# sign_controller.net
KiCad netlist of a schematic drawn in Altium Designer
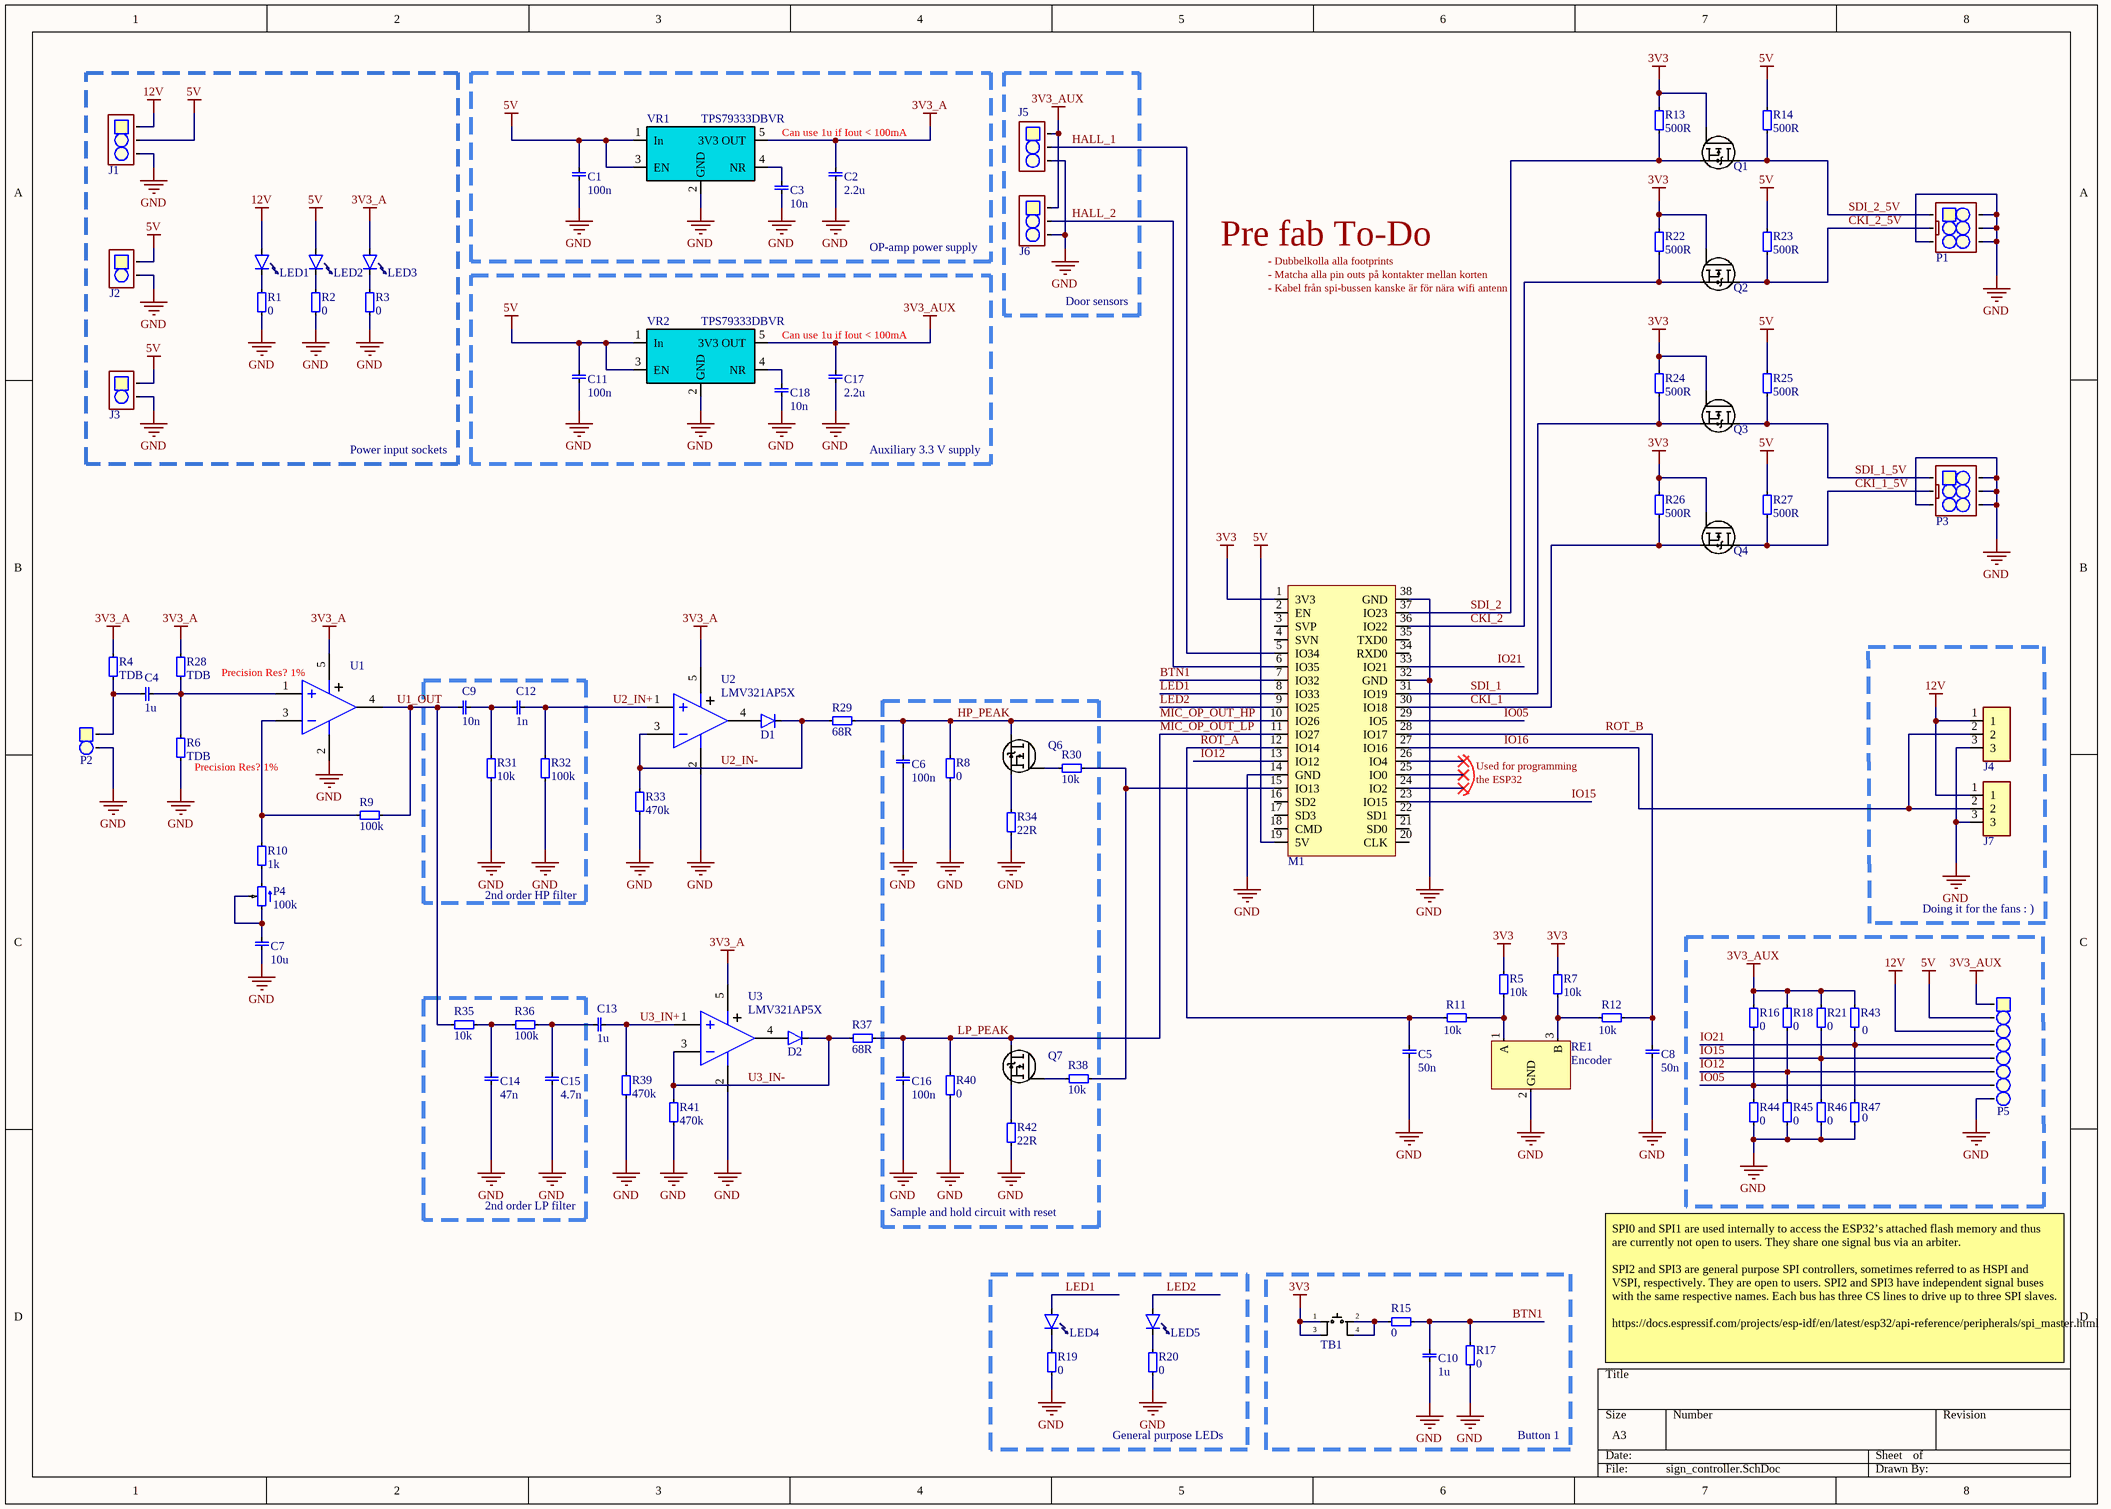
[diagram p0: sign_controller.SchDoc]

(export (version "E")
  (design (tool "Eeschema 10.0.6"))
  (components
    (comp (ref "C1")
      (value "100n")
      (footprint "0603 cap")
      (fields (field (name "Comment") "0603, capacitor"))
      (libsource (lib "sign_lib") (part "0603, capacitor"))
    )
    (comp (ref "C2")
      (value "2.2u")
      (footprint "1206, capasitor")
      (fields (field (name "Comment") "1206, capacitor"))
      (libsource (lib "sign_lib") (part "1206, capacitor"))
    )
    (comp (ref "C3")
      (value "10n")
      (footprint "0603 cap")
      (fields (field (name "Comment") "0603, capacitor"))
      (libsource (lib "sign_lib") (part "0603, capacitor"))
    )
    (comp (ref "C4")
      (value "1u")
      (footprint "1206, capasitor")
      (fields (field (name "Comment") "1206, capacitor"))
      (libsource (lib "sign_lib") (part "1206, capacitor"))
    )
    (comp (ref "C5")
      (value "50n")
      (footprint "0603 cap")
      (fields (field (name "Comment") "0603, capacitor"))
      (libsource (lib "sign_lib") (part "0603, capacitor"))
    )
    (comp (ref "C6")
      (value "100n")
      (footprint "0603 cap")
      (fields (field (name "Comment") "0603, capacitor"))
      (libsource (lib "sign_lib") (part "0603, capacitor"))
    )
    (comp (ref "C7")
      (value "10u")
      (footprint "1206, capasitor")
      (fields (field (name "Comment") "1206, capacitor"))
      (libsource (lib "sign_lib") (part "1206, capacitor"))
    )
    (comp (ref "C8")
      (value "50n")
      (footprint "0603 cap")
      (fields (field (name "Comment") "0603, capacitor"))
      (libsource (lib "sign_lib") (part "0603, capacitor"))
    )
    (comp (ref "C9")
      (value "10n")
      (footprint "0603 cap")
      (fields (field (name "Comment") "0603, capacitor"))
      (libsource (lib "sign_lib") (part "0603, capacitor"))
    )
    (comp (ref "C10")
      (value "1u")
      (footprint "0603 cap")
      (fields (field (name "Comment") "0603, capacitor"))
      (libsource (lib "jclib") (part "0603, capacitor"))
    )
    (comp (ref "C11")
      (value "100n")
      (footprint "0603 cap")
      (fields (field (name "Comment") "0603, capacitor"))
      (libsource (lib "sign_lib") (part "0603, capacitor"))
    )
    (comp (ref "C12")
      (value "1n")
      (footprint "0603 cap")
      (fields (field (name "Comment") "0603, capacitor"))
      (libsource (lib "sign_lib") (part "0603, capacitor"))
    )
    (comp (ref "C13")
      (value "1u")
      (footprint "0603 cap")
      (fields (field (name "Comment") "0603, capacitor"))
      (libsource (lib "sign_lib") (part "0603, capacitor"))
    )
    (comp (ref "C14")
      (value "47n")
      (footprint "0603 cap")
      (fields (field (name "Comment") "0603, capacitor"))
      (libsource (lib "sign_lib") (part "0603, capacitor"))
    )
    (comp (ref "C15")
      (value "4.7n")
      (footprint "0603 cap")
      (fields (field (name "Comment") "0603, capacitor"))
      (libsource (lib "sign_lib") (part "0603, capacitor"))
    )
    (comp (ref "C16")
      (value "100n")
      (footprint "0603 cap")
      (fields (field (name "Comment") "0603, capacitor"))
      (libsource (lib "sign_lib") (part "0603, capacitor"))
    )
    (comp (ref "C17")
      (value "2.2u")
      (footprint "1206, capasitor")
      (fields (field (name "Comment") "1206, capacitor"))
      (libsource (lib "sign_lib") (part "1206, capacitor"))
    )
    (comp (ref "C18")
      (value "10n")
      (footprint "0603 cap")
      (fields (field (name "Comment") "0603, capacitor"))
      (libsource (lib "sign_lib") (part "0603, capacitor"))
    )
    (comp (ref "D1")
      (value "BAT18")
      (footprint "SOT23")
      (description "Electrokit art: 40311018, 100mA, Vf 1.2V, 35V")
      (libsource (lib "sign_lib") (part "Diode SMD"))
    )
    (comp (ref "D2")
      (value "BAT18")
      (footprint "SOT23")
      (description "Electrokit art: 40311018, 100mA, Vf 1.2V, 35V")
      (libsource (lib "sign_lib") (part "Diode SMD"))
    )
    (comp (ref "J1")
      (value "3 Pole MSTBA Connector")
      (footprint "3POLE_MSTBA_ANGLE")
      (libsource (lib "sign_lib") (part "3 Pole MSTBA Connector"))
    )
    (comp (ref "J2")
      (value "2 Pole MSTBA Connector")
      (footprint "2POLE_MSTBA_ANGLE")
      (libsource (lib "sign_lib") (part "2 Pole MSTBA Connector"))
    )
    (comp (ref "J3")
      (value "2 Pole MSTBA Connector")
      (footprint "2POLE_MSTBA_ANGLE")
      (libsource (lib "sign_lib") (part "2 Pole MSTBA Connector"))
    )
    (comp (ref "J4")
      (value "PicoBlade, 3 pos")
      (footprint "MOLEX_0530470310")
      (libsource (lib "exensor_lib") (part "PicoBlade, 3 pos"))
    )
    (comp (ref "J5")
      (value "3 Pole MSTBA Connector")
      (footprint "3POLE_MSTBA_ANGLE")
      (libsource (lib "sign_lib") (part "3 Pole MSTBA Connector"))
    )
    (comp (ref "J6")
      (value "3 Pole MSTBA Connector")
      (footprint "3POLE_MSTBA_ANGLE")
      (libsource (lib "sign_lib") (part "3 Pole MSTBA Connector"))
    )
    (comp (ref "J7")
      (value "PicoBlade, 3 pos")
      (footprint "MOLEX_0530470310")
      (libsource (lib "exensor_lib") (part "PicoBlade, 3 pos"))
    )
    (comp (ref "LED1")
      (value "0805, LED")
      (footprint "0805_led")
      (libsource (lib "sign_lib") (part "0805, LED"))
    )
    (comp (ref "LED2")
      (value "0805, LED")
      (footprint "0805_led")
      (libsource (lib "sign_lib") (part "0805, LED"))
    )
    (comp (ref "LED3")
      (value "0805, LED")
      (footprint "0805_led")
      (libsource (lib "sign_lib") (part "0805, LED"))
    )
    (comp (ref "LED4")
      (value "0805, LED")
      (footprint "0805_led")
      (libsource (lib "sign_lib") (part "0805, LED"))
    )
    (comp (ref "LED5")
      (value "0805, LED")
      (footprint "0805_led")
      (libsource (lib "sign_lib") (part "0805, LED"))
    )
    (comp (ref "M1")
      (value "ESP32-DEVKITC-32D-F")
      (footprint "ESP32_DEVKITC")
      (libsource (lib "sign_lib") (part "ESP32-DEVKITC-32D-F"))
    )
    (comp (ref "P1")
      (value "2x3 Pin Header")
      (footprint "2x3 PH")
      (description "2x3 Ribbon connector")
      (libsource (lib "sign_lib") (part "2x3 Ribbon connector"))
    )
    (comp (ref "P2")
      (value "1x2 Pin Header")
      (footprint "padtwo_L")
      (description "2.54 mm, TH")
      (libsource (lib "sign_lib") (part "1x2 Pin Header"))
    )
    (comp (ref "P3")
      (value "2x3 Pin Header")
      (footprint "2x3 PH")
      (description "2x3 Ribbon connector")
      (libsource (lib "sign_lib") (part "2x3 Ribbon connector"))
    )
    (comp (ref "P4")
      (value "100k")
      (footprint "POT_TH1")
      (fields (field (name "Comment") "Pot"))
      (libsource (lib "sign_lib") (part "Pot"))
    )
    (comp (ref "P5")
      (value "1x8 Pin Header")
      (footprint "1x8 Pin HEader")
      (description "2.54 mm")
      (libsource (lib "sign_lib") (part "1x8 Pin Header"))
    )
    (comp (ref "Q1")
      (value "BSS138")
      (footprint "SOT323")
      (description "N-Channel Logic Level Enhancement Mode Field Effect Transistor")
      (libsource (lib "sign_lib") (part "BSS138"))
    )
    (comp (ref "Q2")
      (value "BSS138")
      (footprint "SOT323")
      (description "N-Channel Logic Level Enhancement Mode Field Effect Transistor")
      (libsource (lib "sign_lib") (part "BSS138"))
    )
    (comp (ref "Q3")
      (value "BSS138")
      (footprint "SOT323")
      (description "N-Channel Logic Level Enhancement Mode Field Effect Transistor")
      (libsource (lib "sign_lib") (part "BSS138"))
    )
    (comp (ref "Q4")
      (value "BSS138")
      (footprint "SOT323")
      (description "N-Channel Logic Level Enhancement Mode Field Effect Transistor")
      (libsource (lib "sign_lib") (part "BSS138"))
    )
    (comp (ref "Q6")
      (value "BSS138")
      (footprint "SOT323")
      (description "N-Channel Logic Level Enhancement Mode Field Effect Transistor")
      (libsource (lib "sign_lib") (part "BSS138"))
    )
    (comp (ref "Q7")
      (value "BSS138")
      (footprint "SOT323")
      (description "N-Channel Logic Level Enhancement Mode Field Effect Transistor")
      (libsource (lib "sign_lib") (part "BSS138"))
    )
    (comp (ref "R1")
      (value "0")
      (footprint "0603")
      (fields (field (name "Comment") "0603, resistor"))
      (libsource (lib "sign_lib") (part "0603, resistor"))
    )
    (comp (ref "R2")
      (value "0")
      (footprint "0603")
      (fields (field (name "Comment") "0603, resistor"))
      (libsource (lib "sign_lib") (part "0603, resistor"))
    )
    (comp (ref "R3")
      (value "0")
      (footprint "0603")
      (fields (field (name "Comment") "0603, resistor"))
      (libsource (lib "sign_lib") (part "0603, resistor"))
    )
    (comp (ref "R4")
      (value "TDB")
      (footprint "0603")
      (fields (field (name "Comment") "0603, resistor"))
      (libsource (lib "sign_lib") (part "0603, resistor"))
    )
    (comp (ref "R5")
      (value "10k")
      (footprint "0603")
      (fields (field (name "Comment") "0603, resistor"))
      (libsource (lib "sign_lib") (part "0603, resistor"))
    )
    (comp (ref "R6")
      (value "TDB")
      (footprint "0603")
      (fields (field (name "Comment") "0603, resistor"))
      (libsource (lib "sign_lib") (part "0603, resistor"))
    )
    (comp (ref "R7")
      (value "10k")
      (footprint "0603")
      (fields (field (name "Comment") "0603, resistor"))
      (libsource (lib "sign_lib") (part "0603, resistor"))
    )
    (comp (ref "R8")
      (value "0")
      (footprint "0603")
      (fields (field (name "Comment") "0603, resistor"))
      (libsource (lib "sign_lib") (part "0603, resistor"))
    )
    (comp (ref "R9")
      (value "100k")
      (footprint "0603")
      (fields (field (name "Comment") "0603, resistor"))
      (libsource (lib "sign_lib") (part "0603, resistor"))
    )
    (comp (ref "R10")
      (value "1k")
      (footprint "0603")
      (fields (field (name "Comment") "0603, resistor"))
      (libsource (lib "sign_lib") (part "0603, resistor"))
    )
    (comp (ref "R11")
      (value "10k")
      (footprint "0603")
      (fields (field (name "Comment") "0603, resistor"))
      (libsource (lib "sign_lib") (part "0603, resistor"))
    )
    (comp (ref "R12")
      (value "10k")
      (footprint "0603")
      (fields (field (name "Comment") "0603, resistor"))
      (libsource (lib "sign_lib") (part "0603, resistor"))
    )
    (comp (ref "R13")
      (value "500R")
      (footprint "0603")
      (fields (field (name "Comment") "0603, resistor"))
      (libsource (lib "sign_lib") (part "0603, resistor"))
    )
    (comp (ref "R14")
      (value "500R")
      (footprint "0603")
      (fields (field (name "Comment") "0603, resistor"))
      (libsource (lib "sign_lib") (part "0603, resistor"))
    )
    (comp (ref "R15")
      (value "0")
      (footprint "0603")
      (fields (field (name "Comment") "0603, resistor"))
      (libsource (lib "sign_lib") (part "0603, resistor"))
    )
    (comp (ref "R16")
      (value "0")
      (footprint "0603")
      (fields (field (name "Comment") "0603, resistor"))
      (libsource (lib "sign_lib") (part "0603, resistor"))
    )
    (comp (ref "R17")
      (value "0")
      (footprint "0603")
      (fields (field (name "Comment") "0603, resistor"))
      (libsource (lib "sign_lib") (part "0603, resistor"))
    )
    (comp (ref "R18")
      (value "0")
      (footprint "0603")
      (fields (field (name "Comment") "0603, resistor"))
      (libsource (lib "sign_lib") (part "0603, resistor"))
    )
    (comp (ref "R19")
      (value "0")
      (footprint "0603")
      (fields (field (name "Comment") "0603, resistor"))
      (libsource (lib "sign_lib") (part "0603, resistor"))
    )
    (comp (ref "R20")
      (value "0")
      (footprint "0603")
      (fields (field (name "Comment") "0603, resistor"))
      (libsource (lib "sign_lib") (part "0603, resistor"))
    )
    (comp (ref "R21")
      (value "0")
      (footprint "0603")
      (fields (field (name "Comment") "0603, resistor"))
      (libsource (lib "sign_lib") (part "0603, resistor"))
    )
    (comp (ref "R22")
      (value "500R")
      (footprint "0603")
      (fields (field (name "Comment") "0603, resistor"))
      (libsource (lib "sign_lib") (part "0603, resistor"))
    )
    (comp (ref "R23")
      (value "500R")
      (footprint "0603")
      (fields (field (name "Comment") "0603, resistor"))
      (libsource (lib "sign_lib") (part "0603, resistor"))
    )
    (comp (ref "R24")
      (value "500R")
      (footprint "0603")
      (fields (field (name "Comment") "0603, resistor"))
      (libsource (lib "sign_lib") (part "0603, resistor"))
    )
    (comp (ref "R25")
      (value "500R")
      (footprint "0603")
      (fields (field (name "Comment") "0603, resistor"))
      (libsource (lib "sign_lib") (part "0603, resistor"))
    )
    (comp (ref "R26")
      (value "500R")
      (footprint "0603")
      (fields (field (name "Comment") "0603, resistor"))
      (libsource (lib "sign_lib") (part "0603, resistor"))
    )
    (comp (ref "R27")
      (value "500R")
      (footprint "0603")
      (fields (field (name "Comment") "0603, resistor"))
      (libsource (lib "sign_lib") (part "0603, resistor"))
    )
    (comp (ref "R28")
      (value "TDB")
      (footprint "0603")
      (fields (field (name "Comment") "0603, resistor"))
      (libsource (lib "sign_lib") (part "0603, resistor"))
    )
    (comp (ref "R29")
      (value "68R")
      (footprint "0603")
      (fields (field (name "Comment") "0603, resistor"))
      (libsource (lib "sign_lib") (part "0603, resistor"))
    )
    (comp (ref "R30")
      (value "10k")
      (footprint "0603")
      (fields (field (name "Comment") "0603, resistor"))
      (libsource (lib "sign_lib") (part "0603, resistor"))
    )
    (comp (ref "R31")
      (value "10k")
      (footprint "0603")
      (fields (field (name "Comment") "0603, resistor"))
      (libsource (lib "sign_lib") (part "0603, resistor"))
    )
    (comp (ref "R32")
      (value "100k")
      (footprint "0603")
      (fields (field (name "Comment") "0603, resistor"))
      (libsource (lib "sign_lib") (part "0603, resistor"))
    )
    (comp (ref "R33")
      (value "470k")
      (footprint "0603")
      (fields (field (name "Comment") "0603, resistor"))
      (libsource (lib "sign_lib") (part "0603, resistor"))
    )
    (comp (ref "R34")
      (value "22R")
      (footprint "0603")
      (fields (field (name "Comment") "0603, resistor"))
      (libsource (lib "sign_lib") (part "0603, resistor"))
    )
    (comp (ref "R35")
      (value "10k")
      (footprint "0603")
      (fields (field (name "Comment") "0603, resistor"))
      (libsource (lib "sign_lib") (part "0603, resistor"))
    )
    (comp (ref "R36")
      (value "100k")
      (footprint "0603")
      (fields (field (name "Comment") "0603, resistor"))
      (libsource (lib "sign_lib") (part "0603, resistor"))
    )
    (comp (ref "R37")
      (value "68R")
      (footprint "0603")
      (fields (field (name "Comment") "0603, resistor"))
      (libsource (lib "sign_lib") (part "0603, resistor"))
    )
    (comp (ref "R38")
      (value "10k")
      (footprint "0603")
      (fields (field (name "Comment") "0603, resistor"))
      (libsource (lib "sign_lib") (part "0603, resistor"))
    )
    (comp (ref "R39")
      (value "470k")
      (footprint "0603")
      (fields (field (name "Comment") "0603, resistor"))
      (libsource (lib "sign_lib") (part "0603, resistor"))
    )
    (comp (ref "R40")
      (value "0")
      (footprint "0603")
      (fields (field (name "Comment") "0603, resistor"))
      (libsource (lib "sign_lib") (part "0603, resistor"))
    )
    (comp (ref "R41")
      (value "470k")
      (footprint "0603")
      (fields (field (name "Comment") "0603, resistor"))
      (libsource (lib "sign_lib") (part "0603, resistor"))
    )
    (comp (ref "R42")
      (value "22R")
      (footprint "0603")
      (fields (field (name "Comment") "0603, resistor"))
      (libsource (lib "sign_lib") (part "0603, resistor"))
    )
    (comp (ref "R43")
      (value "0")
      (footprint "0603")
      (fields (field (name "Comment") "0603, resistor"))
      (libsource (lib "sign_lib") (part "0603, resistor"))
    )
    (comp (ref "R44")
      (value "0")
      (footprint "0603")
      (fields (field (name "Comment") "0603, resistor"))
      (libsource (lib "sign_lib") (part "0603, resistor"))
    )
    (comp (ref "R45")
      (value "0")
      (footprint "0603")
      (fields (field (name "Comment") "0603, resistor"))
      (libsource (lib "sign_lib") (part "0603, resistor"))
    )
    (comp (ref "R46")
      (value "0")
      (footprint "0603")
      (fields (field (name "Comment") "0603, resistor"))
      (libsource (lib "sign_lib") (part "0603, resistor"))
    )
    (comp (ref "R47")
      (value "0")
      (footprint "0603")
      (fields (field (name "Comment") "0603, resistor"))
      (libsource (lib "sign_lib") (part "0603, resistor"))
    )
    (comp (ref "RE1")
      (value "Encoder")
      (footprint "RotaryEncoder")
      (libsource (lib "sign_lib") (part "RotaryEncoder"))
    )
    (comp (ref "TB1")
      (value "Tactile Button")
      (footprint "tacButton smd")
      (description "Tactile Switch Small Low")
      (libsource (lib "sign_lib") (part "TacButton SMD"))
    )
    (comp (ref "U1")
      (value "LMV321AP5X")
      (footprint "SOT23-5")
      (description "Operational Amplifier, Low Power, Rail to Rail Output, CMOS Op-Amp")
      (fields (field (name "MANUFACTURER") "ON Semiconductor / Fairchild"))
      (libsource (lib "sign_lib") (part "LMV321AP5X"))
    )
    (comp (ref "U2")
      (value "LMV321AP5X")
      (footprint "SOT23-5")
      (description "Operational Amplifier, Low Power, Rail to Rail Output, CMOS Op-Amp")
      (fields (field (name "MANUFACTURER") "ON Semiconductor / Fairchild"))
      (libsource (lib "sign_lib") (part "LMV321AP5X"))
    )
    (comp (ref "U3")
      (value "LMV321AP5X")
      (footprint "SOT23-5")
      (description "Operational Amplifier, Low Power, Rail to Rail Output, CMOS Op-Amp")
      (fields (field (name "MANUFACTURER") "ON Semiconductor / Fairchild"))
      (libsource (lib "sign_lib") (part "LMV321AP5X"))
    )
    (comp (ref "VR1")
      (value "TPS79333DBVR")
      (footprint "SOT23-5")
      (description "Low Dropout Regulators(LDO) Positive Fixed 180mV @ 200mA 5.5V 3.3V 200mA SOT-23-5 RoHS")
      (fields (field (name "MANUFACTURER") "Texas Instruments"))
      (libsource (lib "sign_lib") (part "TPS79333DBVR"))
    )
    (comp (ref "VR2")
      (value "TPS79333DBVR")
      (footprint "SOT23-5")
      (description "Low Dropout Regulators(LDO) Positive Fixed 180mV @ 200mA 5.5V 3.3V 200mA SOT-23-5 RoHS")
      (fields (field (name "MANUFACTURER") "Texas Instruments"))
      (libsource (lib "sign_lib") (part "TPS79333DBVR"))
    )
  )
  (nets
    (net (code "1") (name "/BTN1") (class "Default")
      (node (ref "C10") (pin "1") (pinfunction "1_1") (pintype "passive"))
      (node (ref "M1") (pin "7") (pinfunction "IO32_7") (pintype "passive"))
      (node (ref "R15") (pin "0") (pinfunction "0_0") (pintype "passive"))
      (node (ref "R17") (pin "0") (pinfunction "0_0") (pintype "passive"))
    )
    (net (code "2") (name "/CKI_1") (class "Default")
      (node (ref "M1") (pin "30") (pinfunction "IO18_30") (pintype "passive"))
      (node (ref "Q4") (pin "2") (pinfunction "S_2") (pintype "passive"))
      (node (ref "R26") (pin "0") (pinfunction "0_0") (pintype "passive"))
    )
    (net (code "3") (name "/CKI_1_5V") (class "Default")
      (node (ref "P3") (pin "2") (pinfunction "2_2") (pintype "passive"))
      (node (ref "Q4") (pin "3") (pinfunction "D_3") (pintype "passive"))
      (node (ref "R27") (pin "0") (pinfunction "0_0") (pintype "passive"))
    )
    (net (code "4") (name "/CKI_2") (class "Default")
      (node (ref "M1") (pin "36") (pinfunction "IO22_36") (pintype "passive"))
      (node (ref "Q2") (pin "2") (pinfunction "S_2") (pintype "passive"))
      (node (ref "R22") (pin "0") (pinfunction "0_0") (pintype "passive"))
    )
    (net (code "5") (name "/CKI_2_5V") (class "Default")
      (node (ref "P1") (pin "2") (pinfunction "2_2") (pintype "passive"))
      (node (ref "Q2") (pin "3") (pinfunction "D_3") (pintype "passive"))
      (node (ref "R23") (pin "0") (pinfunction "0_0") (pintype "passive"))
    )
    (net (code "6") (name "/HALL_1") (class "Default")
      (node (ref "J5") (pin "2") (pinfunction "2_2") (pintype "passive"))
      (node (ref "M1") (pin "5") (pinfunction "IO34_5") (pintype "passive"))
    )
    (net (code "7") (name "/HALL_2") (class "Default")
      (node (ref "J6") (pin "2") (pinfunction "2_2") (pintype "passive"))
      (node (ref "M1") (pin "6") (pinfunction "IO35_6") (pintype "passive"))
    )
    (net (code "8") (name "/HP_PEAK") (class "Default")
      (node (ref "C6") (pin "1") (pinfunction "1_1") (pintype "passive"))
      (node (ref "M1") (pin "10") (pinfunction "IO26_10") (pintype "passive"))
      (node (ref "Q6") (pin "3") (pinfunction "D_3") (pintype "passive"))
      (node (ref "R29") (pin "1") (pinfunction "1_1") (pintype "passive"))
      (node (ref "R8") (pin "0") (pinfunction "0_0") (pintype "passive"))
    )
    (net (code "9") (name "/IO05") (class "Default")
      (node (ref "M1") (pin "29") (pinfunction "IO5_29") (pintype "passive"))
      (node (ref "P5") (pin "7") (pinfunction "7_7") (pintype "passive"))
      (node (ref "R16") (pin "1") (pinfunction "1_1") (pintype "passive"))
      (node (ref "R44") (pin "0") (pinfunction "0_0") (pintype "passive"))
    )
    (net (code "10") (name "/IO12") (class "Default")
      (node (ref "M1") (pin "13") (pinfunction "IO12_13") (pintype "passive"))
      (node (ref "P5") (pin "6") (pinfunction "6_6") (pintype "passive"))
      (node (ref "R18") (pin "1") (pinfunction "1_1") (pintype "passive"))
      (node (ref "R45") (pin "0") (pinfunction "0_0") (pintype "passive"))
    )
    (net (code "11") (name "/IO15") (class "Default")
      (node (ref "M1") (pin "23") (pinfunction "IO15_23") (pintype "passive"))
      (node (ref "P5") (pin "5") (pinfunction "5_5") (pintype "passive"))
      (node (ref "R21") (pin "1") (pinfunction "1_1") (pintype "passive"))
      (node (ref "R46") (pin "0") (pinfunction "0_0") (pintype "passive"))
    )
    (net (code "12") (name "/IO16") (class "Default")
      (node (ref "J4") (pin "2") (pinfunction "2_2") (pintype "passive"))
      (node (ref "J7") (pin "2") (pinfunction "2_2") (pintype "passive"))
      (node (ref "M1") (pin "27") (pinfunction "IO16_27") (pintype "passive"))
    )
    (net (code "13") (name "/IO21") (class "Default")
      (node (ref "M1") (pin "33") (pinfunction "IO21_33") (pintype "passive"))
      (node (ref "P5") (pin "4") (pinfunction "4_4") (pintype "passive"))
      (node (ref "R43") (pin "1") (pinfunction "1_1") (pintype "passive"))
      (node (ref "R47") (pin "0") (pinfunction "0_0") (pintype "passive"))
    )
    (net (code "14") (name "/LED1") (class "Default")
      (node (ref "LED4") (pin "1") (pinfunction "1_1") (pintype "passive"))
      (node (ref "M1") (pin "8") (pinfunction "IO33_8") (pintype "passive"))
    )
    (net (code "15") (name "/LED2") (class "Default")
      (node (ref "LED5") (pin "1") (pinfunction "1_1") (pintype "passive"))
      (node (ref "M1") (pin "9") (pinfunction "IO25_9") (pintype "passive"))
    )
    (net (code "16") (name "/LP_PEAK") (class "Default")
      (node (ref "C16") (pin "1") (pinfunction "1_1") (pintype "passive"))
      (node (ref "M1") (pin "11") (pinfunction "IO27_11") (pintype "passive"))
      (node (ref "Q7") (pin "3") (pinfunction "D_3") (pintype "passive"))
      (node (ref "R37") (pin "1") (pinfunction "1_1") (pintype "passive"))
      (node (ref "R40") (pin "0") (pinfunction "0_0") (pintype "passive"))
    )
    (net (code "17") (name "/ROT_A") (class "Default")
      (node (ref "C5") (pin "1") (pinfunction "1_1") (pintype "passive"))
      (node (ref "M1") (pin "12") (pinfunction "IO14_12") (pintype "passive"))
      (node (ref "R11") (pin "0") (pinfunction "0_0") (pintype "passive"))
    )
    (net (code "18") (name "/ROT_B") (class "Default")
      (node (ref "C8") (pin "1") (pinfunction "1_1") (pintype "passive"))
      (node (ref "M1") (pin "28") (pinfunction "IO17_28") (pintype "passive"))
      (node (ref "R12") (pin "0") (pinfunction "0_0") (pintype "passive"))
    )
    (net (code "19") (name "/SDI_1") (class "Default")
      (node (ref "M1") (pin "31") (pinfunction "IO19_31") (pintype "passive"))
      (node (ref "Q3") (pin "2") (pinfunction "S_2") (pintype "passive"))
      (node (ref "R24") (pin "0") (pinfunction "0_0") (pintype "passive"))
    )
    (net (code "20") (name "/SDI_1_5V") (class "Default")
      (node (ref "P3") (pin "1") (pinfunction "1_1") (pintype "passive"))
      (node (ref "Q3") (pin "3") (pinfunction "D_3") (pintype "passive"))
      (node (ref "R25") (pin "0") (pinfunction "0_0") (pintype "passive"))
    )
    (net (code "21") (name "/SDI_2") (class "Default")
      (node (ref "M1") (pin "37") (pinfunction "IO23_37") (pintype "passive"))
      (node (ref "Q1") (pin "2") (pinfunction "S_2") (pintype "passive"))
      (node (ref "R13") (pin "0") (pinfunction "0_0") (pintype "passive"))
    )
    (net (code "22") (name "/SDI_2_5V") (class "Default")
      (node (ref "P1") (pin "1") (pinfunction "1_1") (pintype "passive"))
      (node (ref "Q1") (pin "3") (pinfunction "D_3") (pintype "passive"))
      (node (ref "R14") (pin "0") (pinfunction "0_0") (pintype "passive"))
    )
    (net (code "23") (name "/U1_OUT") (class "Default")
      (node (ref "C9") (pin "1") (pinfunction "1_1") (pintype "passive"))
      (node (ref "R35") (pin "0") (pinfunction "0_0") (pintype "passive"))
      (node (ref "R9") (pin "1") (pinfunction "1_1") (pintype "passive"))
      (node (ref "U1") (pin "4") (pinfunction "OUT_4") (pintype "passive"))
    )
    (net (code "24") (name "/U2_IN+") (class "Default")
      (node (ref "C12") (pin "0") (pinfunction "0_0") (pintype "passive"))
      (node (ref "R32") (pin "0") (pinfunction "0_0") (pintype "passive"))
      (node (ref "U2") (pin "1") (pinfunction "IN+_1") (pintype "passive"))
    )
    (net (code "25") (name "/U2_IN-") (class "Default")
      (node (ref "D1") (pin "3") (pinfunction "3_3") (pintype "passive"))
      (node (ref "R29") (pin "0") (pinfunction "0_0") (pintype "passive"))
      (node (ref "R33") (pin "0") (pinfunction "0_0") (pintype "passive"))
      (node (ref "U2") (pin "3") (pinfunction "IN-_3") (pintype "passive"))
    )
    (net (code "26") (name "/U3_IN+") (class "Default")
      (node (ref "C13") (pin "0") (pinfunction "0_0") (pintype "passive"))
      (node (ref "R39") (pin "0") (pinfunction "0_0") (pintype "passive"))
      (node (ref "U3") (pin "1") (pinfunction "IN+_1") (pintype "passive"))
    )
    (net (code "27") (name "/U3_IN-") (class "Default")
      (node (ref "D2") (pin "3") (pinfunction "3_3") (pintype "passive"))
      (node (ref "R37") (pin "0") (pinfunction "0_0") (pintype "passive"))
      (node (ref "R41") (pin "0") (pinfunction "0_0") (pintype "passive"))
      (node (ref "U3") (pin "3") (pinfunction "IN-_3") (pintype "passive"))
    )
    (net (code "28") (name "3V3") (class "Default")
      (node (ref "M1") (pin "1") (pinfunction "3V3_1") (pintype "passive"))
      (node (ref "Q1") (pin "1") (pinfunction "G_1") (pintype "passive"))
      (node (ref "Q2") (pin "1") (pinfunction "G_1") (pintype "passive"))
      (node (ref "Q3") (pin "1") (pinfunction "G_1") (pintype "passive"))
      (node (ref "Q4") (pin "1") (pinfunction "G_1") (pintype "passive"))
      (node (ref "R13") (pin "1") (pinfunction "1_1") (pintype "passive"))
      (node (ref "R22") (pin "1") (pinfunction "1_1") (pintype "passive"))
      (node (ref "R24") (pin "1") (pinfunction "1_1") (pintype "passive"))
      (node (ref "R26") (pin "1") (pinfunction "1_1") (pintype "passive"))
      (node (ref "R5") (pin "1") (pinfunction "1_1") (pintype "passive"))
      (node (ref "R7") (pin "1") (pinfunction "1_1") (pintype "passive"))
      (node (ref "TB1") (pin "1") (pinfunction "1_1") (pintype "passive"))
      (node (ref "TB1") (pin "3") (pinfunction "3_3") (pintype "passive"))
    )
    (net (code "29") (name "3V3_A") (class "Default")
      (node (ref "C2") (pin "1") (pinfunction "1_1") (pintype "passive"))
      (node (ref "LED3") (pin "1") (pinfunction "1_1") (pintype "passive"))
      (node (ref "R28") (pin "1") (pinfunction "1_1") (pintype "passive"))
      (node (ref "R4") (pin "0") (pinfunction "0_0") (pintype "passive"))
      (node (ref "U1") (pin "5") (pinfunction "V+_5") (pintype "power_in"))
      (node (ref "U2") (pin "5") (pinfunction "V+_5") (pintype "power_in"))
      (node (ref "U3") (pin "5") (pinfunction "V+_5") (pintype "power_in"))
      (node (ref "VR1") (pin "5") (pinfunction "3V3_OUT_5") (pintype "passive"))
    )
    (net (code "30") (name "3V3_AUX") (class "Default")
      (node (ref "C17") (pin "1") (pinfunction "1_1") (pintype "passive"))
      (node (ref "J5") (pin "1") (pinfunction "1_1") (pintype "passive"))
      (node (ref "J6") (pin "1") (pinfunction "1_1") (pintype "passive"))
      (node (ref "P5") (pin "1") (pinfunction "1_1") (pintype "passive"))
      (node (ref "R16") (pin "0") (pinfunction "0_0") (pintype "passive"))
      (node (ref "R18") (pin "0") (pinfunction "0_0") (pintype "passive"))
      (node (ref "R21") (pin "0") (pinfunction "0_0") (pintype "passive"))
      (node (ref "R43") (pin "0") (pinfunction "0_0") (pintype "passive"))
      (node (ref "VR2") (pin "5") (pinfunction "3V3_OUT_5") (pintype "passive"))
    )
    (net (code "31") (name "5V") (class "Default")
      (node (ref "C1") (pin "1") (pinfunction "1_1") (pintype "passive"))
      (node (ref "C11") (pin "1") (pinfunction "1_1") (pintype "passive"))
      (node (ref "J1") (pin "2") (pinfunction "2_2") (pintype "passive"))
      (node (ref "J2") (pin "1") (pinfunction "1_1") (pintype "passive"))
      (node (ref "J3") (pin "1") (pinfunction "1_1") (pintype "passive"))
      (node (ref "LED2") (pin "1") (pinfunction "1_1") (pintype "passive"))
      (node (ref "M1") (pin "19") (pinfunction "5V_19") (pintype "passive"))
      (node (ref "P5") (pin "2") (pinfunction "2_2") (pintype "passive"))
      (node (ref "R14") (pin "1") (pinfunction "1_1") (pintype "passive"))
      (node (ref "R23") (pin "1") (pinfunction "1_1") (pintype "passive"))
      (node (ref "R25") (pin "1") (pinfunction "1_1") (pintype "passive"))
      (node (ref "R27") (pin "1") (pinfunction "1_1") (pintype "passive"))
      (node (ref "VR1") (pin "1") (pinfunction "In_1") (pintype "passive"))
      (node (ref "VR1") (pin "3") (pinfunction "EN_3") (pintype "passive"))
      (node (ref "VR2") (pin "1") (pinfunction "In_1") (pintype "passive"))
      (node (ref "VR2") (pin "3") (pinfunction "EN_3") (pintype "passive"))
    )
    (net (code "32") (name "12V") (class "Default")
      (node (ref "J1") (pin "1") (pinfunction "1_1") (pintype "passive"))
      (node (ref "J4") (pin "1") (pinfunction "1_1") (pintype "passive"))
      (node (ref "J7") (pin "1") (pinfunction "1_1") (pintype "passive"))
      (node (ref "LED1") (pin "1") (pinfunction "1_1") (pintype "passive"))
      (node (ref "P5") (pin "3") (pinfunction "3_3") (pintype "passive"))
    )
    (net (code "33") (name "GND") (class "Default")
      (node (ref "C1") (pin "0") (pinfunction "0_0") (pintype "passive"))
      (node (ref "C10") (pin "0") (pinfunction "0_0") (pintype "passive"))
      (node (ref "C11") (pin "0") (pinfunction "0_0") (pintype "passive"))
      (node (ref "C14") (pin "1") (pinfunction "1_1") (pintype "passive"))
      (node (ref "C15") (pin "1") (pinfunction "1_1") (pintype "passive"))
      (node (ref "C16") (pin "0") (pinfunction "0_0") (pintype "passive"))
      (node (ref "C17") (pin "0") (pinfunction "0_0") (pintype "passive"))
      (node (ref "C18") (pin "0") (pinfunction "0_0") (pintype "passive"))
      (node (ref "C2") (pin "0") (pinfunction "0_0") (pintype "passive"))
      (node (ref "C3") (pin "0") (pinfunction "0_0") (pintype "passive"))
      (node (ref "C5") (pin "0") (pinfunction "0_0") (pintype "passive"))
      (node (ref "C6") (pin "0") (pinfunction "0_0") (pintype "passive"))
      (node (ref "C7") (pin "0") (pinfunction "0_0") (pintype "passive"))
      (node (ref "C8") (pin "0") (pinfunction "0_0") (pintype "passive"))
      (node (ref "J1") (pin "3") (pinfunction "3_3") (pintype "passive"))
      (node (ref "J2") (pin "2") (pinfunction "2_2") (pintype "passive"))
      (node (ref "J3") (pin "2") (pinfunction "2_2") (pintype "passive"))
      (node (ref "J4") (pin "3") (pinfunction "3_3") (pintype "passive"))
      (node (ref "J5") (pin "3") (pinfunction "3_3") (pintype "passive"))
      (node (ref "J6") (pin "3") (pinfunction "3_3") (pintype "passive"))
      (node (ref "J7") (pin "3") (pinfunction "3_3") (pintype "passive"))
      (node (ref "M1") (pin "14") (pinfunction "GND_14") (pintype "passive"))
      (node (ref "M1") (pin "32") (pinfunction "GND_32") (pintype "passive"))
      (node (ref "M1") (pin "38") (pinfunction "GND_38") (pintype "passive"))
      (node (ref "P1") (pin "3") (pinfunction "3_3") (pintype "passive"))
      (node (ref "P1") (pin "4") (pinfunction "4_4") (pintype "passive"))
      (node (ref "P1") (pin "5") (pinfunction "5_5") (pintype "passive"))
      (node (ref "P1") (pin "6") (pinfunction "6_6") (pintype "passive"))
      (node (ref "P2") (pin "2") (pinfunction "2_2") (pintype "passive"))
      (node (ref "P3") (pin "3") (pinfunction "3_3") (pintype "passive"))
      (node (ref "P3") (pin "4") (pinfunction "4_4") (pintype "passive"))
      (node (ref "P3") (pin "5") (pinfunction "5_5") (pintype "passive"))
      (node (ref "P3") (pin "6") (pinfunction "6_6") (pintype "passive"))
      (node (ref "P5") (pin "8") (pinfunction "8_8") (pintype "passive"))
      (node (ref "R1") (pin "1") (pinfunction "1_1") (pintype "passive"))
      (node (ref "R17") (pin "1") (pinfunction "1_1") (pintype "passive"))
      (node (ref "R19") (pin "1") (pinfunction "1_1") (pintype "passive"))
      (node (ref "R2") (pin "1") (pinfunction "1_1") (pintype "passive"))
      (node (ref "R20") (pin "1") (pinfunction "1_1") (pintype "passive"))
      (node (ref "R3") (pin "1") (pinfunction "1_1") (pintype "passive"))
      (node (ref "R31") (pin "1") (pinfunction "1_1") (pintype "passive"))
      (node (ref "R32") (pin "1") (pinfunction "1_1") (pintype "passive"))
      (node (ref "R33") (pin "1") (pinfunction "1_1") (pintype "passive"))
      (node (ref "R34") (pin "1") (pinfunction "1_1") (pintype "passive"))
      (node (ref "R39") (pin "1") (pinfunction "1_1") (pintype "passive"))
      (node (ref "R40") (pin "1") (pinfunction "1_1") (pintype "passive"))
      (node (ref "R41") (pin "1") (pinfunction "1_1") (pintype "passive"))
      (node (ref "R42") (pin "1") (pinfunction "1_1") (pintype "passive"))
      (node (ref "R44") (pin "1") (pinfunction "1_1") (pintype "passive"))
      (node (ref "R45") (pin "1") (pinfunction "1_1") (pintype "passive"))
      (node (ref "R46") (pin "1") (pinfunction "1_1") (pintype "passive"))
      (node (ref "R47") (pin "1") (pinfunction "1_1") (pintype "passive"))
      (node (ref "R6") (pin "1") (pinfunction "1_1") (pintype "passive"))
      (node (ref "R8") (pin "1") (pinfunction "1_1") (pintype "passive"))
      (node (ref "RE1") (pin "2") (pinfunction "GND_2") (pintype "passive"))
      (node (ref "U1") (pin "2") (pinfunction "V-_2") (pintype "power_in"))
      (node (ref "U2") (pin "2") (pinfunction "V-_2") (pintype "power_in"))
      (node (ref "U3") (pin "2") (pinfunction "V-_2") (pintype "power_in"))
      (node (ref "VR1") (pin "2") (pinfunction "GND_2") (pintype "passive"))
      (node (ref "VR2") (pin "2") (pinfunction "GND_2") (pintype "passive"))
    )
    (net (code "34") (name "Net-(C4-Pad1)") (class "Default")
      (node (ref "C4") (pin "1") (pinfunction "1_1") (pintype "passive"))
      (node (ref "P2") (pin "1") (pinfunction "1_1") (pintype "passive"))
      (node (ref "R4") (pin "1") (pinfunction "1_1") (pintype "passive"))
    )
    (net (code "35") (name "Net-(C7-Pad1)") (class "Default")
      (node (ref "C7") (pin "1") (pinfunction "1_1") (pintype "passive"))
      (node (ref "P4") (pin "1") (pinfunction "1_1") (pintype "passive"))
      (node (ref "P4") (pin "2") (pinfunction "2_2") (pintype "passive"))
    )
    (net (code "36") (name "Net-(C12-Pad1)") (class "Default")
      (node (ref "C12") (pin "1") (pinfunction "1_1") (pintype "passive"))
      (node (ref "C9") (pin "0") (pinfunction "0_0") (pintype "passive"))
      (node (ref "R31") (pin "0") (pinfunction "0_0") (pintype "passive"))
    )
    (net (code "37") (name "Net-(C13-Pad1)") (class "Default")
      (node (ref "C13") (pin "1") (pinfunction "1_1") (pintype "passive"))
      (node (ref "C15") (pin "0") (pinfunction "0_0") (pintype "passive"))
      (node (ref "R36") (pin "1") (pinfunction "1_1") (pintype "passive"))
    )
    (net (code "38") (name "Net-(C14-Pad0)") (class "Default")
      (node (ref "C14") (pin "0") (pinfunction "0_0") (pintype "passive"))
      (node (ref "R35") (pin "1") (pinfunction "1_1") (pintype "passive"))
      (node (ref "R36") (pin "0") (pinfunction "0_0") (pintype "passive"))
    )
    (net (code "39") (name "Net-(LED1-Cathode)") (class "Default")
      (node (ref "LED1") (pin "0") (pinfunction "Cathode_0") (pintype "passive"))
      (node (ref "R1") (pin "0") (pinfunction "0_0") (pintype "passive"))
    )
    (net (code "40") (name "Net-(LED2-Cathode)") (class "Default")
      (node (ref "LED2") (pin "0") (pinfunction "Cathode_0") (pintype "passive"))
      (node (ref "R2") (pin "0") (pinfunction "0_0") (pintype "passive"))
    )
    (net (code "41") (name "Net-(LED3-Cathode)") (class "Default")
      (node (ref "LED3") (pin "0") (pinfunction "Cathode_0") (pintype "passive"))
      (node (ref "R3") (pin "0") (pinfunction "0_0") (pintype "passive"))
    )
    (net (code "42") (name "Net-(LED4-Cathode)") (class "Default")
      (node (ref "LED4") (pin "0") (pinfunction "Cathode_0") (pintype "passive"))
      (node (ref "R19") (pin "0") (pinfunction "0_0") (pintype "passive"))
    )
    (net (code "43") (name "Net-(LED5-Cathode)") (class "Default")
      (node (ref "LED5") (pin "0") (pinfunction "Cathode_0") (pintype "passive"))
      (node (ref "R20") (pin "0") (pinfunction "0_0") (pintype "passive"))
    )
    (net (code "44") (name "Net-(M1-IO13)") (class "Default")
      (node (ref "M1") (pin "15") (pinfunction "IO13_15") (pintype "passive"))
      (node (ref "R30") (pin "1") (pinfunction "1_1") (pintype "passive"))
      (node (ref "R38") (pin "1") (pinfunction "1_1") (pintype "passive"))
    )
    (net (code "45") (name "Net-(P4-Pad3)") (class "Default")
      (node (ref "P4") (pin "3") (pinfunction "3_3") (pintype "passive"))
      (node (ref "R10") (pin "1") (pinfunction "1_1") (pintype "passive"))
    )
    (net (code "46") (name "Net-(Q6-G)") (class "Default")
      (node (ref "Q6") (pin "1") (pinfunction "G_1") (pintype "passive"))
      (node (ref "R30") (pin "0") (pinfunction "0_0") (pintype "passive"))
    )
    (net (code "47") (name "Net-(Q6-S)") (class "Default")
      (node (ref "Q6") (pin "2") (pinfunction "S_2") (pintype "passive"))
      (node (ref "R34") (pin "0") (pinfunction "0_0") (pintype "passive"))
    )
    (net (code "48") (name "Net-(Q7-G)") (class "Default")
      (node (ref "Q7") (pin "1") (pinfunction "G_1") (pintype "passive"))
      (node (ref "R38") (pin "0") (pinfunction "0_0") (pintype "passive"))
    )
    (net (code "49") (name "Net-(Q7-S)") (class "Default")
      (node (ref "Q7") (pin "2") (pinfunction "S_2") (pintype "passive"))
      (node (ref "R42") (pin "0") (pinfunction "0_0") (pintype "passive"))
    )
    (net (code "50") (name "Net-(R15-Pad1)") (class "Default")
      (node (ref "R15") (pin "1") (pinfunction "1_1") (pintype "passive"))
      (node (ref "TB1") (pin "2") (pinfunction "2_2") (pintype "passive"))
      (node (ref "TB1") (pin "4") (pinfunction "4_4") (pintype "passive"))
    )
    (net (code "51") (name "Net-(RE1-A)") (class "Default")
      (node (ref "R11") (pin "1") (pinfunction "1_1") (pintype "passive"))
      (node (ref "R5") (pin "0") (pinfunction "0_0") (pintype "passive"))
      (node (ref "RE1") (pin "1") (pinfunction "A_1") (pintype "passive"))
    )
    (net (code "52") (name "Net-(RE1-B)") (class "Default")
      (node (ref "R12") (pin "1") (pinfunction "1_1") (pintype "passive"))
      (node (ref "R7") (pin "0") (pinfunction "0_0") (pintype "passive"))
      (node (ref "RE1") (pin "3") (pinfunction "B_3") (pintype "passive"))
    )
    (net (code "53") (name "Net-(U1-IN+)") (class "Default")
      (node (ref "C4") (pin "0") (pinfunction "0_0") (pintype "passive"))
      (node (ref "R28") (pin "0") (pinfunction "0_0") (pintype "passive"))
      (node (ref "R6") (pin "0") (pinfunction "0_0") (pintype "passive"))
      (node (ref "U1") (pin "1") (pinfunction "IN+_1") (pintype "passive"))
    )
    (net (code "54") (name "Net-(U1-IN-)") (class "Default")
      (node (ref "R10") (pin "0") (pinfunction "0_0") (pintype "passive"))
      (node (ref "R9") (pin "0") (pinfunction "0_0") (pintype "passive"))
      (node (ref "U1") (pin "3") (pinfunction "IN-_3") (pintype "passive"))
    )
    (net (code "55") (name "Net-(U2-OUT)") (class "Default")
      (node (ref "D1") (pin "1") (pinfunction "1_1") (pintype "passive"))
      (node (ref "U2") (pin "4") (pinfunction "OUT_4") (pintype "passive"))
    )
    (net (code "56") (name "Net-(U3-OUT)") (class "Default")
      (node (ref "D2") (pin "1") (pinfunction "1_1") (pintype "passive"))
      (node (ref "U3") (pin "4") (pinfunction "OUT_4") (pintype "passive"))
    )
    (net (code "57") (name "Net-(VR1-NR)") (class "Default")
      (node (ref "C3") (pin "1") (pinfunction "1_1") (pintype "passive"))
      (node (ref "VR1") (pin "4") (pinfunction "NR_4") (pintype "passive"))
    )
    (net (code "58") (name "Net-(VR2-NR)") (class "Default")
      (node (ref "C18") (pin "1") (pinfunction "1_1") (pintype "passive"))
      (node (ref "VR2") (pin "4") (pinfunction "NR_4") (pintype "passive"))
    )
    (net (code "59") (name "unconnected-(M1-CLK-Pad20)") (class "Default")
      (node (ref "M1") (pin "20") (pinfunction "CLK_20") (pintype "passive"))
    )
    (net (code "60") (name "unconnected-(M1-CMD-Pad18)") (class "Default")
      (node (ref "M1") (pin "18") (pinfunction "CMD_18") (pintype "passive"))
    )
    (net (code "61") (name "unconnected-(M1-EN-Pad2)") (class "Default")
      (node (ref "M1") (pin "2") (pinfunction "EN_2") (pintype "passive"))
    )
    (net (code "62") (name "unconnected-(M1-IO0-Pad25)") (class "Default")
      (node (ref "M1") (pin "25") (pinfunction "IO0_25") (pintype "passive+no_connect"))
    )
    (net (code "63") (name "unconnected-(M1-IO2-Pad24)") (class "Default")
      (node (ref "M1") (pin "24") (pinfunction "IO2_24") (pintype "passive+no_connect"))
    )
    (net (code "64") (name "unconnected-(M1-IO4-Pad26)") (class "Default")
      (node (ref "M1") (pin "26") (pinfunction "IO4_26") (pintype "passive+no_connect"))
    )
    (net (code "65") (name "unconnected-(M1-RXD0-Pad34)") (class "Default")
      (node (ref "M1") (pin "34") (pinfunction "RXD0_34") (pintype "passive"))
    )
    (net (code "66") (name "unconnected-(M1-SD0-Pad21)") (class "Default")
      (node (ref "M1") (pin "21") (pinfunction "SD0_21") (pintype "passive"))
    )
    (net (code "67") (name "unconnected-(M1-SD1-Pad22)") (class "Default")
      (node (ref "M1") (pin "22") (pinfunction "SD1_22") (pintype "passive"))
    )
    (net (code "68") (name "unconnected-(M1-SD2-Pad16)") (class "Default")
      (node (ref "M1") (pin "16") (pinfunction "SD2_16") (pintype "passive"))
    )
    (net (code "69") (name "unconnected-(M1-SD3-Pad17)") (class "Default")
      (node (ref "M1") (pin "17") (pinfunction "SD3_17") (pintype "passive"))
    )
    (net (code "70") (name "unconnected-(M1-SVN-Pad4)") (class "Default")
      (node (ref "M1") (pin "4") (pinfunction "SVN_4") (pintype "passive"))
    )
    (net (code "71") (name "unconnected-(M1-SVP-Pad3)") (class "Default")
      (node (ref "M1") (pin "3") (pinfunction "SVP_3") (pintype "passive"))
    )
    (net (code "72") (name "unconnected-(M1-TXD0-Pad35)") (class "Default")
      (node (ref "M1") (pin "35") (pinfunction "TXD0_35") (pintype "passive"))
    )
  )
)
